# avrNetStack.net
KiCad netlist of a schematic drawn in EAGLE
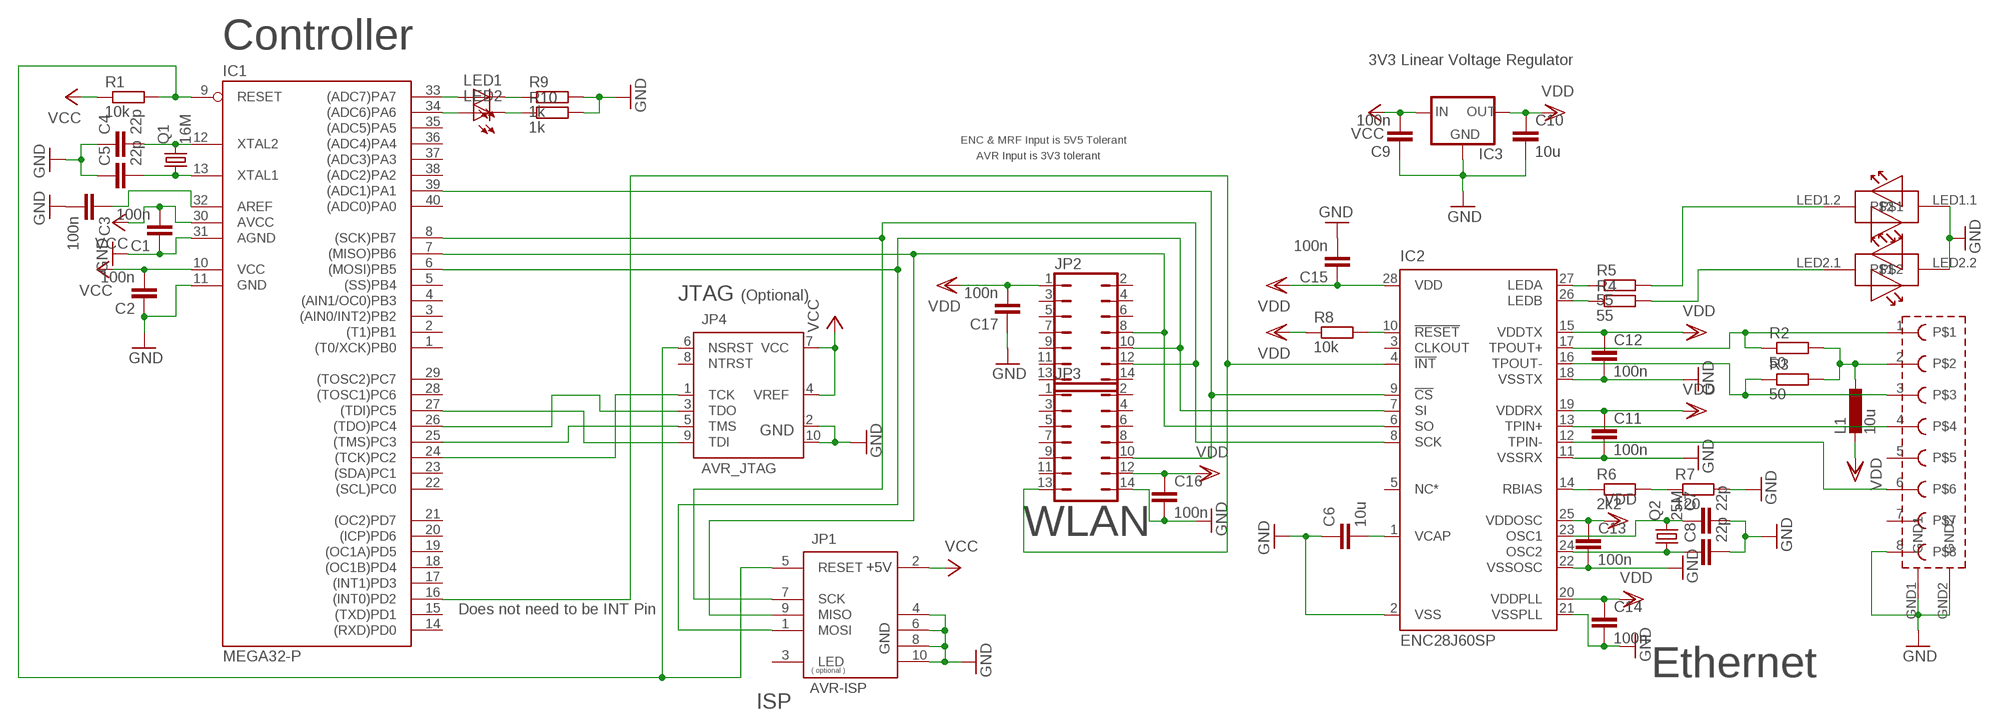
[diagram p0: schematic, sheet 1]

(export (version "E")
  (design (tool "Eeschema 10.0.6"))
  (components
    (comp (ref "C1")
      (value "100n")
      (footprint "eagle-import:C025-030X050")
      (libsource (lib "eagle-import") (part "C-EU025-030X050"))
    )
    (comp (ref "C2")
      (value "100n")
      (footprint "eagle-import:C025-030X050")
      (libsource (lib "eagle-import") (part "C-EU025-030X050"))
    )
    (comp (ref "C3")
      (value "100n")
      (footprint "eagle-import:C025-030X050")
      (libsource (lib "eagle-import") (part "C-EU025-030X050"))
    )
    (comp (ref "C4")
      (value "22p")
      (footprint "eagle-import:C025-030X050")
      (libsource (lib "eagle-import") (part "C-EU025-030X050"))
    )
    (comp (ref "C5")
      (value "22p")
      (footprint "eagle-import:C025-030X050")
      (libsource (lib "eagle-import") (part "C-EU025-030X050"))
    )
    (comp (ref "C6")
      (value "10u")
      (footprint "eagle-import:C025-030X050")
      (libsource (lib "eagle-import") (part "C-EU025-030X050"))
    )
    (comp (ref "C7")
      (value "22p")
      (footprint "eagle-import:C025-030X050")
      (libsource (lib "eagle-import") (part "C-EU025-030X050"))
    )
    (comp (ref "C8")
      (value "22p")
      (footprint "eagle-import:C025-030X050")
      (libsource (lib "eagle-import") (part "C-EU025-030X050"))
    )
    (comp (ref "C9")
      (value "100n")
      (footprint "eagle-import:C025-030X050")
      (libsource (lib "eagle-import") (part "C-EU025-030X050"))
    )
    (comp (ref "C10")
      (value "10u")
      (footprint "eagle-import:C025-030X050")
      (libsource (lib "eagle-import") (part "C-EU025-030X050"))
    )
    (comp (ref "C11")
      (value "100n")
      (footprint "eagle-import:C025-030X050")
      (libsource (lib "eagle-import") (part "C-EU025-030X050"))
    )
    (comp (ref "C12")
      (value "100n")
      (footprint "eagle-import:C025-030X050")
      (libsource (lib "eagle-import") (part "C-EU025-030X050"))
    )
    (comp (ref "C13")
      (value "100n")
      (footprint "eagle-import:C025-030X050")
      (libsource (lib "eagle-import") (part "C-EU025-030X050"))
    )
    (comp (ref "C14")
      (value "100n")
      (footprint "eagle-import:C025-030X050")
      (libsource (lib "eagle-import") (part "C-EU025-030X050"))
    )
    (comp (ref "C15")
      (value "100n")
      (footprint "eagle-import:C025-030X050")
      (libsource (lib "eagle-import") (part "C-EU025-030X050"))
    )
    (comp (ref "C16")
      (value "100n")
      (footprint "eagle-import:C025-030X050")
      (libsource (lib "eagle-import") (part "C-EU025-030X050"))
    )
    (comp (ref "C17")
      (value "100n")
      (footprint "eagle-import:C025-030X050")
      (libsource (lib "eagle-import") (part "C-EU025-030X050"))
    )
    (comp (ref "IC1")
      (value "MEGA32-P")
      (footprint "eagle-import:DIL40")
      (libsource (lib "eagle-import") (part "MEGA32-P"))
    )
    (comp (ref "IC2")
      (value "ENC28J60SP")
      (footprint "eagle-import:DIL28-3")
      (fields (field (name "MF") "MICROCHIP") (field (name "MPN") "ENC28J60/SP"))
      (libsource (lib "eagle-import") (part "ENC28J60SP"))
    )
    (comp (ref "IC3")
      (value "78XXS")
      (footprint "eagle-import:78XXS")
      (libsource (lib "eagle-import") (part "78XXS"))
    )
    (comp (ref "JP1")
      (value "AVR-ISP")
      (footprint "eagle-import:ML10")
      (libsource (lib "eagle-import") (part "AVR-ISP"))
    )
    (comp (ref "JP2")
      (value "JP7Q")
      (footprint "eagle-import:JP7Q")
      (libsource (lib "eagle-import") (part "JP7Q"))
    )
    (comp (ref "JP3")
      (value "JP7Q")
      (footprint "eagle-import:JP7Q")
      (libsource (lib "eagle-import") (part "JP7Q"))
    )
    (comp (ref "JP4")
      (value "AVR_JTAG")
      (footprint "eagle-import:ML10")
      (libsource (lib "eagle-import") (part "AVR_JTAG"))
    )
    (comp (ref "L1")
      (value "10u")
      (footprint "eagle-import:0204_7")
      (libsource (lib "eagle-import") (part "L-EU0204/7"))
    )
    (comp (ref "LED1")
      (value "LED5MM")
      (footprint "eagle-import:LED5MM")
      (libsource (lib "eagle-import") (part "LED5MM"))
    )
    (comp (ref "LED2")
      (value "LED5MM")
      (footprint "eagle-import:LED5MM")
      (libsource (lib "eagle-import") (part "LED5MM"))
    )
    (comp (ref "Q1")
      (value "16M")
      (footprint "eagle-import:HC49_S")
      (libsource (lib "eagle-import") (part "CRYSTALHC49S"))
    )
    (comp (ref "Q2")
      (value "25M")
      (footprint "eagle-import:HC49_S")
      (libsource (lib "eagle-import") (part "CRYSTALHC49S"))
    )
    (comp (ref "R1")
      (value "10k")
      (footprint "eagle-import:0204_7")
      (libsource (lib "eagle-import") (part "R-EU_0204/7"))
    )
    (comp (ref "R2")
      (value "50")
      (footprint "eagle-import:0204_7")
      (libsource (lib "eagle-import") (part "R-EU_0204/7"))
    )
    (comp (ref "R3")
      (value "50")
      (footprint "eagle-import:0204_7")
      (libsource (lib "eagle-import") (part "R-EU_0204/7"))
    )
    (comp (ref "R4")
      (value "55")
      (footprint "eagle-import:0204_7")
      (libsource (lib "eagle-import") (part "R-EU_0204/7"))
    )
    (comp (ref "R5")
      (value "55")
      (footprint "eagle-import:0204_7")
      (libsource (lib "eagle-import") (part "R-EU_0204/7"))
    )
    (comp (ref "R6")
      (value "2k2")
      (footprint "eagle-import:0204_7")
      (libsource (lib "eagle-import") (part "R-EU_0204/7"))
    )
    (comp (ref "R7")
      (value "120")
      (footprint "eagle-import:0204_7")
      (libsource (lib "eagle-import") (part "R-EU_0204/7"))
    )
    (comp (ref "R8")
      (value "10k")
      (footprint "eagle-import:0204_7")
      (libsource (lib "eagle-import") (part "R-EU_0204/7"))
    )
    (comp (ref "R9")
      (value "1k")
      (footprint "eagle-import:0204_7")
      (libsource (lib "eagle-import") (part "R-EU_0204/7"))
    )
    (comp (ref "R10")
      (value "1k")
      (footprint "eagle-import:0204_7")
      (libsource (lib "eagle-import") (part "R-EU_0204/7"))
    )
    (comp (ref "U$1")
      (value "MAGJACK")
      (footprint "eagle-import:MAGJACK")
      (libsource (lib "eagle-import") (part "MAGJACK"))
    )
  )
  (nets
    (net (code "1") (name "GND") (class "Default")
      (node (ref "C1") (pin "1") (pinfunction "1_1") (pintype "passive"))
      (node (ref "C10") (pin "2") (pinfunction "2_2") (pintype "passive"))
      (node (ref "C11") (pin "2") (pinfunction "2_2") (pintype "passive"))
      (node (ref "C12") (pin "2") (pinfunction "2_2") (pintype "passive"))
      (node (ref "C13") (pin "2") (pinfunction "2_2") (pintype "passive"))
      (node (ref "C14") (pin "2") (pinfunction "2_2") (pintype "passive"))
      (node (ref "C15") (pin "2") (pinfunction "2_2") (pintype "passive"))
      (node (ref "C16") (pin "2") (pinfunction "2_2") (pintype "passive"))
      (node (ref "C17") (pin "1") (pinfunction "1_1") (pintype "passive"))
      (node (ref "C2") (pin "1") (pinfunction "1_1") (pintype "passive"))
      (node (ref "C3") (pin "2") (pinfunction "2_2") (pintype "passive"))
      (node (ref "C4") (pin "1") (pinfunction "1_1") (pintype "passive"))
      (node (ref "C5") (pin "1") (pinfunction "1_1") (pintype "passive"))
      (node (ref "C6") (pin "1") (pinfunction "1_1") (pintype "passive"))
      (node (ref "C7") (pin "2") (pinfunction "2_2") (pintype "passive"))
      (node (ref "C8") (pin "2") (pinfunction "2_2") (pintype "passive"))
      (node (ref "C9") (pin "1") (pinfunction "1_1") (pintype "passive"))
      (node (ref "IC1") (pin "11") (pinfunction "GND_11") (pintype "power_in"))
      (node (ref "IC1") (pin "31") (pinfunction "AGND_31") (pintype "power_in"))
      (node (ref "IC2") (pin "11") (pinfunction "VSSRX_11") (pintype "input"))
      (node (ref "IC2") (pin "18") (pinfunction "VSSTX_18") (pintype "input"))
      (node (ref "IC2") (pin "2") (pinfunction "VSS_2") (pintype "input"))
      (node (ref "IC2") (pin "21") (pinfunction "VSSPLL_21") (pintype "input"))
      (node (ref "IC2") (pin "22") (pinfunction "VSSOSC_22") (pintype "input"))
      (node (ref "IC3") (pin "GND") (pinfunction "GND_GND") (pintype "input"))
      (node (ref "JP1") (pin "10") (pinfunction "GND_10") (pintype "power_in"))
      (node (ref "JP1") (pin "4") (pinfunction "GND_4") (pintype "power_in"))
      (node (ref "JP1") (pin "6") (pinfunction "GND_6") (pintype "power_in"))
      (node (ref "JP1") (pin "8") (pinfunction "GND_8") (pintype "power_in"))
      (node (ref "JP3") (pin "14") (pinfunction "14_14") (pintype "passive"))
      (node (ref "JP4") (pin "10") (pinfunction "GND_10") (pintype "power_in"))
      (node (ref "JP4") (pin "2") (pinfunction "GND_2") (pintype "power_in"))
      (node (ref "R10") (pin "2") (pinfunction "2_2") (pintype "passive"))
      (node (ref "R7") (pin "2") (pinfunction "2_2") (pintype "passive"))
      (node (ref "R9") (pin "2") (pinfunction "2_2") (pintype "passive"))
      (node (ref "U$1") (pin "8") (pinfunction "P$8_8") (pintype "passive"))
      (node (ref "U$1") (pin "GND1") (pinfunction "GND1_GND1") (pintype "passive"))
      (node (ref "U$1") (pin "GND2") (pinfunction "GND2_GND2") (pintype "passive"))
      (node (ref "U$1") (pin "LED1.1") (pinfunction "P$1_LED1.1") (pintype "passive"))
      (node (ref "U$1") (pin "LED2.2") (pinfunction "P$2_LED2.2") (pintype "passive"))
    )
    (net (code "2") (name "Net-(IC1-(ADC1)PA1)") (class "Default")
      (node (ref "IC1") (pin "39") (pinfunction "(ADC1)PA1_39") (pintype "bidirectional"))
      (node (ref "IC2") (pin "9") (pinfunction "~{CS}_9") (pintype "input"))
      (node (ref "JP3") (pin "10") (pinfunction "10_10") (pintype "passive"))
    )
    (net (code "3") (name "Net-(IC1-(ADC6)PA6)") (class "Default")
      (node (ref "IC1") (pin "34") (pinfunction "(ADC6)PA6_34") (pintype "bidirectional"))
      (node (ref "LED2") (pin "A") (pinfunction "A_A") (pintype "passive"))
    )
    (net (code "4") (name "Net-(IC1-(ADC7)PA7)") (class "Default")
      (node (ref "IC1") (pin "33") (pinfunction "(ADC7)PA7_33") (pintype "bidirectional"))
      (node (ref "LED1") (pin "A") (pinfunction "A_A") (pintype "passive"))
    )
    (net (code "5") (name "Net-(IC1-(INT0)PD2)") (class "Default")
      (node (ref "IC1") (pin "16") (pinfunction "(INT0)PD2_16") (pintype "bidirectional"))
      (node (ref "IC2") (pin "4") (pinfunction "~{INT}_4") (pintype "output"))
      (node (ref "JP3") (pin "13") (pinfunction "13_13") (pintype "passive"))
    )
    (net (code "6") (name "Net-(IC1-(MISO)PB6)") (class "Default")
      (node (ref "IC1") (pin "7") (pinfunction "(MISO)PB6_7") (pintype "bidirectional"))
      (node (ref "IC2") (pin "6") (pinfunction "SO_6") (pintype "output"))
      (node (ref "JP1") (pin "9") (pinfunction "MISO_9") (pintype "bidirectional"))
      (node (ref "JP2") (pin "8") (pinfunction "8_8") (pintype "passive"))
    )
    (net (code "7") (name "Net-(IC1-(MOSI)PB5)") (class "Default")
      (node (ref "IC1") (pin "6") (pinfunction "(MOSI)PB5_6") (pintype "bidirectional"))
      (node (ref "IC2") (pin "7") (pinfunction "SI_7") (pintype "input"))
      (node (ref "JP1") (pin "1") (pinfunction "MOSI_1") (pintype "bidirectional"))
      (node (ref "JP2") (pin "10") (pinfunction "10_10") (pintype "passive"))
    )
    (net (code "8") (name "Net-(IC1-(SCK)PB7)") (class "Default")
      (node (ref "IC1") (pin "8") (pinfunction "(SCK)PB7_8") (pintype "bidirectional"))
      (node (ref "IC2") (pin "8") (pinfunction "SCK_8") (pintype "input"))
      (node (ref "JP1") (pin "7") (pinfunction "SCK_7") (pintype "input"))
      (node (ref "JP2") (pin "12") (pinfunction "12_12") (pintype "passive"))
    )
    (net (code "9") (name "Net-(IC1-(TCK)PC2)") (class "Default")
      (node (ref "IC1") (pin "24") (pinfunction "(TCK)PC2_24") (pintype "bidirectional"))
      (node (ref "JP4") (pin "1") (pinfunction "TCK_1") (pintype "bidirectional"))
    )
    (net (code "10") (name "Net-(IC1-(TDI)PC5)") (class "Default")
      (node (ref "IC1") (pin "27") (pinfunction "(TDI)PC5_27") (pintype "bidirectional"))
      (node (ref "JP4") (pin "9") (pinfunction "TDI_9") (pintype "bidirectional"))
    )
    (net (code "11") (name "Net-(IC1-(TDO)PC4)") (class "Default")
      (node (ref "IC1") (pin "26") (pinfunction "(TDO)PC4_26") (pintype "bidirectional"))
      (node (ref "JP4") (pin "3") (pinfunction "TDO_3") (pintype "bidirectional"))
    )
    (net (code "12") (name "Net-(IC1-(TMS)PC3)") (class "Default")
      (node (ref "IC1") (pin "25") (pinfunction "(TMS)PC3_25") (pintype "bidirectional"))
      (node (ref "JP4") (pin "5") (pinfunction "TMS_5") (pintype "bidirectional"))
    )
    (net (code "13") (name "Net-(IC1-AREF)") (class "Default")
      (node (ref "C3") (pin "1") (pinfunction "1_1") (pintype "passive"))
      (node (ref "IC1") (pin "32") (pinfunction "AREF_32") (pintype "power_in"))
    )
    (net (code "14") (name "Net-(IC1-RESET)") (class "Default")
      (node (ref "IC1") (pin "9") (pinfunction "RESET_9") (pintype "input"))
      (node (ref "JP1") (pin "5") (pinfunction "RESET_5") (pintype "input"))
      (node (ref "JP4") (pin "6") (pinfunction "NSRST_6") (pintype "bidirectional"))
      (node (ref "R1") (pin "2") (pinfunction "2_2") (pintype "passive"))
    )
    (net (code "15") (name "Net-(IC1-XTAL1)") (class "Default")
      (node (ref "C5") (pin "2") (pinfunction "2_2") (pintype "passive"))
      (node (ref "IC1") (pin "13") (pinfunction "XTAL1_13") (pintype "bidirectional"))
      (node (ref "Q1") (pin "1") (pinfunction "1_1") (pintype "passive"))
    )
    (net (code "16") (name "Net-(IC1-XTAL2)") (class "Default")
      (node (ref "C4") (pin "2") (pinfunction "2_2") (pintype "passive"))
      (node (ref "IC1") (pin "12") (pinfunction "XTAL2_12") (pintype "bidirectional"))
      (node (ref "Q1") (pin "2") (pinfunction "2_2") (pintype "passive"))
    )
    (net (code "17") (name "Net-(IC2-LEDA)") (class "Default")
      (node (ref "IC2") (pin "27") (pinfunction "LEDA_27") (pintype "output"))
      (node (ref "R5") (pin "1") (pinfunction "1_1") (pintype "passive"))
    )
    (net (code "18") (name "Net-(IC2-LEDB)") (class "Default")
      (node (ref "IC2") (pin "26") (pinfunction "LEDB_26") (pintype "output"))
      (node (ref "R4") (pin "1") (pinfunction "1_1") (pintype "passive"))
    )
    (net (code "19") (name "Net-(IC2-OSC1)") (class "Default")
      (node (ref "C7") (pin "1") (pinfunction "1_1") (pintype "passive"))
      (node (ref "IC2") (pin "23") (pinfunction "OSC1_23") (pintype "input"))
      (node (ref "Q2") (pin "2") (pinfunction "2_2") (pintype "passive"))
    )
    (net (code "20") (name "Net-(IC2-OSC2)") (class "Default")
      (node (ref "C8") (pin "1") (pinfunction "1_1") (pintype "passive"))
      (node (ref "IC2") (pin "24") (pinfunction "OSC2_24") (pintype "output"))
      (node (ref "Q2") (pin "1") (pinfunction "1_1") (pintype "passive"))
    )
    (net (code "21") (name "Net-(IC2-RBIAS)") (class "Default")
      (node (ref "IC2") (pin "14") (pinfunction "RBIAS_14") (pintype "input"))
      (node (ref "R6") (pin "1") (pinfunction "1_1") (pintype "passive"))
    )
    (net (code "22") (name "Net-(IC2-TPIN+)") (class "Default")
      (node (ref "IC2") (pin "13") (pinfunction "TPIN+_13") (pintype "input"))
      (node (ref "U$1") (pin "4") (pinfunction "P$4_4") (pintype "passive"))
    )
    (net (code "23") (name "Net-(IC2-TPIN-)") (class "Default")
      (node (ref "IC2") (pin "12") (pinfunction "TPIN-_12") (pintype "input"))
      (node (ref "U$1") (pin "6") (pinfunction "P$6_6") (pintype "passive"))
    )
    (net (code "24") (name "Net-(IC2-TPOUT+)") (class "Default")
      (node (ref "IC2") (pin "17") (pinfunction "TPOUT+_17") (pintype "output"))
      (node (ref "R2") (pin "1") (pinfunction "1_1") (pintype "passive"))
      (node (ref "U$1") (pin "1") (pinfunction "P$1_1") (pintype "passive"))
    )
    (net (code "25") (name "Net-(IC2-TPOUT-)") (class "Default")
      (node (ref "IC2") (pin "16") (pinfunction "TPOUT-_16") (pintype "output"))
      (node (ref "R3") (pin "1") (pinfunction "1_1") (pintype "passive"))
      (node (ref "U$1") (pin "3") (pinfunction "P$3_3") (pintype "passive"))
    )
    (net (code "26") (name "Net-(IC2-VCAP)") (class "Default")
      (node (ref "C6") (pin "2") (pinfunction "2_2") (pintype "passive"))
      (node (ref "IC2") (pin "1") (pinfunction "VCAP_1") (pintype "input"))
    )
    (net (code "27") (name "Net-(IC2-~{RESET})") (class "Default")
      (node (ref "IC2") (pin "10") (pinfunction "~{RESET}_10") (pintype "input"))
      (node (ref "R8") (pin "2") (pinfunction "2_2") (pintype "passive"))
    )
    (net (code "28") (name "Net-(LED1-C)") (class "Default")
      (node (ref "LED1") (pin "K") (pinfunction "C_K") (pintype "passive"))
      (node (ref "R9") (pin "1") (pinfunction "1_1") (pintype "passive"))
    )
    (net (code "29") (name "Net-(LED2-C)") (class "Default")
      (node (ref "LED2") (pin "K") (pinfunction "C_K") (pintype "passive"))
      (node (ref "R10") (pin "1") (pinfunction "1_1") (pintype "passive"))
    )
    (net (code "30") (name "Net-(R6-Pad2)") (class "Default")
      (node (ref "R6") (pin "2") (pinfunction "2_2") (pintype "passive"))
      (node (ref "R7") (pin "1") (pinfunction "1_1") (pintype "passive"))
    )
    (net (code "31") (name "Net-(U$1A-P$2)") (class "Default")
      (node (ref "L1") (pin "1") (pinfunction "1_1") (pintype "passive"))
      (node (ref "R2") (pin "2") (pinfunction "2_2") (pintype "passive"))
      (node (ref "R3") (pin "2") (pinfunction "2_2") (pintype "passive"))
      (node (ref "U$1") (pin "2") (pinfunction "P$2_2") (pintype "passive"))
    )
    (net (code "32") (name "Net-(U$1B-P$2)") (class "Default")
      (node (ref "R5") (pin "2") (pinfunction "2_2") (pintype "passive"))
      (node (ref "U$1") (pin "LED1.2") (pinfunction "P$2_LED1.2") (pintype "passive"))
    )
    (net (code "33") (name "Net-(U$1C-P$1)") (class "Default")
      (node (ref "R4") (pin "2") (pinfunction "2_2") (pintype "passive"))
      (node (ref "U$1") (pin "LED2.1") (pinfunction "P$1_LED2.1") (pintype "passive"))
    )
    (net (code "34") (name "VCC") (class "Default")
      (node (ref "C1") (pin "2") (pinfunction "2_2") (pintype "passive"))
      (node (ref "C2") (pin "2") (pinfunction "2_2") (pintype "passive"))
      (node (ref "C9") (pin "2") (pinfunction "2_2") (pintype "passive"))
      (node (ref "IC1") (pin "10") (pinfunction "VCC_10") (pintype "power_in"))
      (node (ref "IC1") (pin "30") (pinfunction "AVCC_30") (pintype "power_in"))
      (node (ref "IC3") (pin "IN") (pinfunction "IN_IN") (pintype "input"))
      (node (ref "JP1") (pin "2") (pinfunction "+5V_2") (pintype "power_in"))
      (node (ref "JP4") (pin "4") (pinfunction "VREF_4") (pintype "input"))
      (node (ref "JP4") (pin "7") (pinfunction "VCC_7") (pintype "power_in"))
      (node (ref "R1") (pin "1") (pinfunction "1_1") (pintype "passive"))
    )
    (net (code "35") (name "VDD") (class "Default")
      (node (ref "C10") (pin "1") (pinfunction "1_1") (pintype "passive"))
      (node (ref "C11") (pin "1") (pinfunction "1_1") (pintype "passive"))
      (node (ref "C12") (pin "1") (pinfunction "1_1") (pintype "passive"))
      (node (ref "C13") (pin "1") (pinfunction "1_1") (pintype "passive"))
      (node (ref "C14") (pin "1") (pinfunction "1_1") (pintype "passive"))
      (node (ref "C15") (pin "1") (pinfunction "1_1") (pintype "passive"))
      (node (ref "C16") (pin "1") (pinfunction "1_1") (pintype "passive"))
      (node (ref "C17") (pin "2") (pinfunction "2_2") (pintype "passive"))
      (node (ref "IC2") (pin "15") (pinfunction "VDDTX_15") (pintype "input"))
      (node (ref "IC2") (pin "19") (pinfunction "VDDRX_19") (pintype "input"))
      (node (ref "IC2") (pin "20") (pinfunction "VDDPLL_20") (pintype "input"))
      (node (ref "IC2") (pin "25") (pinfunction "VDDOSC_25") (pintype "input"))
      (node (ref "IC2") (pin "28") (pinfunction "VDD_28") (pintype "input"))
      (node (ref "IC3") (pin "OUT") (pinfunction "OUT_OUT") (pintype "passive"))
      (node (ref "JP2") (pin "1") (pinfunction "1_1") (pintype "passive"))
      (node (ref "JP3") (pin "12") (pinfunction "12_12") (pintype "passive"))
      (node (ref "L1") (pin "2") (pinfunction "2_2") (pintype "passive"))
      (node (ref "R8") (pin "1") (pinfunction "1_1") (pintype "passive"))
    )
    (net (code "36") (name "unconnected-(IC1-(ADC0)PA0-Pad40)") (class "Default")
      (node (ref "IC1") (pin "40") (pinfunction "(ADC0)PA0_40") (pintype "bidirectional"))
    )
    (net (code "37") (name "unconnected-(IC1-(ADC2)PA2-Pad38)") (class "Default")
      (node (ref "IC1") (pin "38") (pinfunction "(ADC2)PA2_38") (pintype "bidirectional"))
    )
    (net (code "38") (name "unconnected-(IC1-(ADC3)PA3-Pad37)") (class "Default")
      (node (ref "IC1") (pin "37") (pinfunction "(ADC3)PA3_37") (pintype "bidirectional"))
    )
    (net (code "39") (name "unconnected-(IC1-(ADC4)PA4-Pad36)") (class "Default")
      (node (ref "IC1") (pin "36") (pinfunction "(ADC4)PA4_36") (pintype "bidirectional"))
    )
    (net (code "40") (name "unconnected-(IC1-(ADC5)PA5-Pad35)") (class "Default")
      (node (ref "IC1") (pin "35") (pinfunction "(ADC5)PA5_35") (pintype "bidirectional"))
    )
    (net (code "41") (name "unconnected-(IC1-(AIN0{slash}INT2)PB2-Pad3)") (class "Default")
      (node (ref "IC1") (pin "3") (pinfunction "(AIN0/INT2)PB2_3") (pintype "bidirectional"))
    )
    (net (code "42") (name "unconnected-(IC1-(AIN1{slash}OC0)PB3-Pad4)") (class "Default")
      (node (ref "IC1") (pin "4") (pinfunction "(AIN1/OC0)PB3_4") (pintype "bidirectional"))
    )
    (net (code "43") (name "unconnected-(IC1-(ICP)PD6-Pad20)") (class "Default")
      (node (ref "IC1") (pin "20") (pinfunction "(ICP)PD6_20") (pintype "bidirectional"))
    )
    (net (code "44") (name "unconnected-(IC1-(INT1)PD3-Pad17)") (class "Default")
      (node (ref "IC1") (pin "17") (pinfunction "(INT1)PD3_17") (pintype "bidirectional"))
    )
    (net (code "45") (name "unconnected-(IC1-(OC1A)PD5-Pad19)") (class "Default")
      (node (ref "IC1") (pin "19") (pinfunction "(OC1A)PD5_19") (pintype "bidirectional"))
    )
    (net (code "46") (name "unconnected-(IC1-(OC1B)PD4-Pad18)") (class "Default")
      (node (ref "IC1") (pin "18") (pinfunction "(OC1B)PD4_18") (pintype "bidirectional"))
    )
    (net (code "47") (name "unconnected-(IC1-(OC2)PD7-Pad21)") (class "Default")
      (node (ref "IC1") (pin "21") (pinfunction "(OC2)PD7_21") (pintype "bidirectional"))
    )
    (net (code "48") (name "unconnected-(IC1-(RXD)PD0-Pad14)") (class "Default")
      (node (ref "IC1") (pin "14") (pinfunction "(RXD)PD0_14") (pintype "bidirectional"))
    )
    (net (code "49") (name "unconnected-(IC1-(SCL)PC0-Pad22)") (class "Default")
      (node (ref "IC1") (pin "22") (pinfunction "(SCL)PC0_22") (pintype "bidirectional"))
    )
    (net (code "50") (name "unconnected-(IC1-(SDA)PC1-Pad23)") (class "Default")
      (node (ref "IC1") (pin "23") (pinfunction "(SDA)PC1_23") (pintype "bidirectional"))
    )
    (net (code "51") (name "unconnected-(IC1-(SS)PB4-Pad5)") (class "Default")
      (node (ref "IC1") (pin "5") (pinfunction "(SS)PB4_5") (pintype "bidirectional"))
    )
    (net (code "52") (name "unconnected-(IC1-(T0{slash}XCK)PB0-Pad1)") (class "Default")
      (node (ref "IC1") (pin "1") (pinfunction "(T0/XCK)PB0_1") (pintype "bidirectional"))
    )
    (net (code "53") (name "unconnected-(IC1-(T1)PB1-Pad2)") (class "Default")
      (node (ref "IC1") (pin "2") (pinfunction "(T1)PB1_2") (pintype "bidirectional"))
    )
    (net (code "54") (name "unconnected-(IC1-(TOSC1)PC6-Pad28)") (class "Default")
      (node (ref "IC1") (pin "28") (pinfunction "(TOSC1)PC6_28") (pintype "bidirectional"))
    )
    (net (code "55") (name "unconnected-(IC1-(TOSC2)PC7-Pad29)") (class "Default")
      (node (ref "IC1") (pin "29") (pinfunction "(TOSC2)PC7_29") (pintype "bidirectional"))
    )
    (net (code "56") (name "unconnected-(IC1-(TXD)PD1-Pad15)") (class "Default")
      (node (ref "IC1") (pin "15") (pinfunction "(TXD)PD1_15") (pintype "bidirectional"))
    )
    (net (code "57") (name "unconnected-(IC2-CLKOUT-Pad3)") (class "Default")
      (node (ref "IC2") (pin "3") (pinfunction "CLKOUT_3") (pintype "output"))
    )
    (net (code "58") (name "unconnected-(IC2-NC*-Pad5)") (class "Default")
      (node (ref "IC2") (pin "5") (pinfunction "NC*_5") (pintype "output"))
    )
    (net (code "59") (name "unconnected-(JP1-LED-Pad3)") (class "Default")
      (node (ref "JP1") (pin "3") (pinfunction "LED_3") (pintype "output"))
    )
    (net (code "60") (name "unconnected-(JP2-Pad2)") (class "Default")
      (node (ref "JP2") (pin "2") (pinfunction "2_2") (pintype "passive"))
    )
    (net (code "61") (name "unconnected-(JP2-Pad3)") (class "Default")
      (node (ref "JP2") (pin "3") (pinfunction "3_3") (pintype "passive"))
    )
    (net (code "62") (name "unconnected-(JP2-Pad4)") (class "Default")
      (node (ref "JP2") (pin "4") (pinfunction "4_4") (pintype "passive"))
    )
    (net (code "63") (name "unconnected-(JP2-Pad5)") (class "Default")
      (node (ref "JP2") (pin "5") (pinfunction "5_5") (pintype "passive"))
    )
    (net (code "64") (name "unconnected-(JP2-Pad6)") (class "Default")
      (node (ref "JP2") (pin "6") (pinfunction "6_6") (pintype "passive"))
    )
    (net (code "65") (name "unconnected-(JP2-Pad7)") (class "Default")
      (node (ref "JP2") (pin "7") (pinfunction "7_7") (pintype "passive"))
    )
    (net (code "66") (name "unconnected-(JP2-Pad9)") (class "Default")
      (node (ref "JP2") (pin "9") (pinfunction "9_9") (pintype "passive"))
    )
    (net (code "67") (name "unconnected-(JP2-Pad11)") (class "Default")
      (node (ref "JP2") (pin "11") (pinfunction "11_11") (pintype "passive"))
    )
    (net (code "68") (name "unconnected-(JP2-Pad13)") (class "Default")
      (node (ref "JP2") (pin "13") (pinfunction "13_13") (pintype "passive"))
    )
    (net (code "69") (name "unconnected-(JP2-Pad14)") (class "Default")
      (node (ref "JP2") (pin "14") (pinfunction "14_14") (pintype "passive"))
    )
    (net (code "70") (name "unconnected-(JP3-Pad1)") (class "Default")
      (node (ref "JP3") (pin "1") (pinfunction "1_1") (pintype "passive"))
    )
    (net (code "71") (name "unconnected-(JP3-Pad2)") (class "Default")
      (node (ref "JP3") (pin "2") (pinfunction "2_2") (pintype "passive"))
    )
    (net (code "72") (name "unconnected-(JP3-Pad3)") (class "Default")
      (node (ref "JP3") (pin "3") (pinfunction "3_3") (pintype "passive"))
    )
    (net (code "73") (name "unconnected-(JP3-Pad4)") (class "Default")
      (node (ref "JP3") (pin "4") (pinfunction "4_4") (pintype "passive"))
    )
    (net (code "74") (name "unconnected-(JP3-Pad5)") (class "Default")
      (node (ref "JP3") (pin "5") (pinfunction "5_5") (pintype "passive"))
    )
    (net (code "75") (name "unconnected-(JP3-Pad6)") (class "Default")
      (node (ref "JP3") (pin "6") (pinfunction "6_6") (pintype "passive"))
    )
    (net (code "76") (name "unconnected-(JP3-Pad7)") (class "Default")
      (node (ref "JP3") (pin "7") (pinfunction "7_7") (pintype "passive"))
    )
    (net (code "77") (name "unconnected-(JP3-Pad8)") (class "Default")
      (node (ref "JP3") (pin "8") (pinfunction "8_8") (pintype "passive"))
    )
    (net (code "78") (name "unconnected-(JP3-Pad9)") (class "Default")
      (node (ref "JP3") (pin "9") (pinfunction "9_9") (pintype "passive"))
    )
    (net (code "79") (name "unconnected-(JP3-Pad11)") (class "Default")
      (node (ref "JP3") (pin "11") (pinfunction "11_11") (pintype "passive"))
    )
    (net (code "80") (name "unconnected-(JP4-NTRST-Pad8)") (class "Default")
      (node (ref "JP4") (pin "8") (pinfunction "NTRST_8") (pintype "bidirectional"))
    )
    (net (code "81") (name "unconnected-(U$1A-P$5-Pad5)") (class "Default")
      (node (ref "U$1") (pin "5") (pinfunction "P$5_5") (pintype "passive"))
    )
    (net (code "82") (name "unconnected-(U$1A-P$7-Pad7)") (class "Default")
      (node (ref "U$1") (pin "7") (pinfunction "P$7_7") (pintype "passive"))
    )
  )
)
